# Opto_outputs.net
KiCad netlist of a schematic drawn in Altium Designer
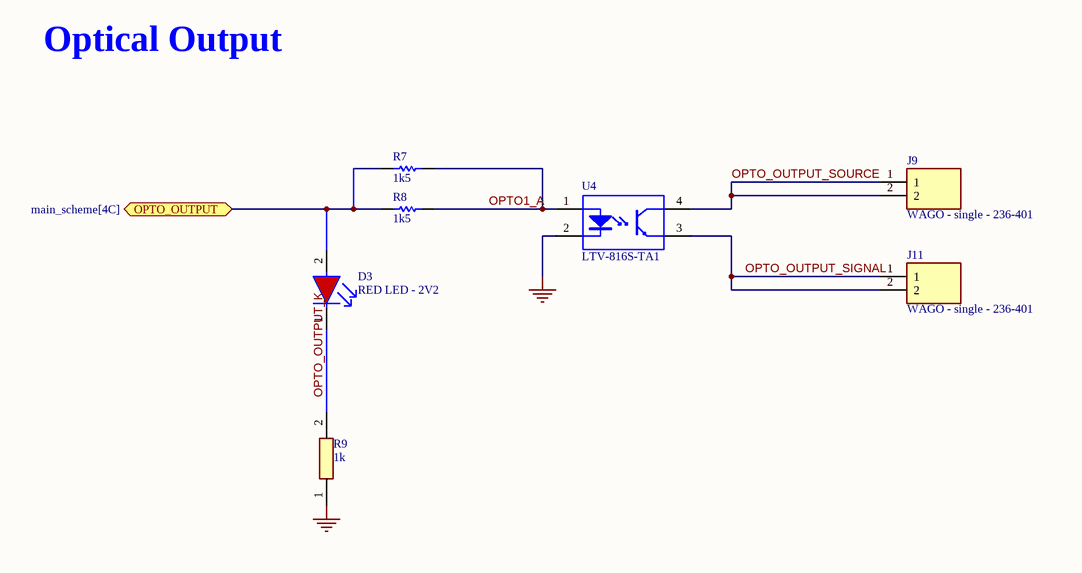
[diagram p0: Opto_outputs.SchDoc]

(export (version "E")
  (design (tool "Eeschema 10.0.6"))
  (components
    (comp (ref "D3")
      (value "RED LED - 2V2")
      (footprint "0603_RED_LED")
      (description "LED RED DIFFUSED 0603 SMD")
      (fields (field (name "PARTNUMBER") "SML-D12U1WT86"))
      (libsource (lib "Schlib1") (part "LED - 0603 - RED - 2V2"))
    )
    (comp (ref "J9")
      (value "WAGO - single - 236-401")
      (footprint "PcbLib1:WAGO-236-601")
      (description "Wago connector - PCB to wire - single - 24A 320V")
      (fields (field (name "PARTNUMBER") "236-401"))
      (libsource (lib "Schlib1") (part "WAGO - single - 236-401"))
    )
    (comp (ref "J11")
      (value "WAGO - single - 236-401")
      (footprint "PcbLib1:WAGO-236-601")
      (description "Wago connector - PCB to wire - single - 24A 320V")
      (fields (field (name "PARTNUMBER") "236-401"))
      (libsource (lib "Schlib1") (part "WAGO - single - 236-401"))
    )
    (comp (ref "R7")
      (value "1k5")
      (footprint "RESC1005X40X25NL05T05")
      (description "Resistor - 0402 - 1k5 - 1% - 100mW")
      (fields (field (name "PARTNUMBER") "ERJ-2RKF1501X"))
      (libsource (lib "Schlib1") (part "Resistor - 0402 - 1k5"))
    )
    (comp (ref "R8")
      (value "1k5")
      (footprint "RESC1005X40X25NL05T05")
      (description "Resistor - 0402 - 1k5 - 1% - 100mW")
      (fields (field (name "PARTNUMBER") "ERJ-2RKF1501X"))
      (libsource (lib "Schlib1") (part "Resistor - 0402 - 1k5"))
    )
    (comp (ref "R9")
      (value "1k")
      (footprint "PcbLib1:0603- SMD resistor")
      (description "Resistor 0603 1KR 100mW 1%")
      (fields (field (name "PARTNUMBER") "RT0603FRE071KL"))
      (libsource (lib "Schlib1") (part "RESISTOR - 0603 - 1k"))
    )
    (comp (ref "U4")
      (value "LTV-816S-TA1")
      (footprint "LTST-LTV-816S_V")
      (description "Photocoupler, 50 mA, -30 to 110 degC, 4-Pin SMD, RoHS, Tape and Reel")
      (libsource (lib "Schlib1") (part "OPTO - 50mA - 80V"))
    )
  )
  (nets
    (net (code "1") (name "/OPTO1_A") (class "Default")
      (node (ref "R7") (pin "2") (pinfunction "2_2") (pintype "passive"))
      (node (ref "R8") (pin "2") (pinfunction "2_2") (pintype "passive"))
      (node (ref "U4") (pin "1") (pinfunction "ANODE_1") (pintype "passive"))
    )
    (net (code "2") (name "/OPTO_OUTPUT") (class "Default")
      (node (ref "D3") (pin "2") (pinfunction "A_2") (pintype "passive"))
      (node (ref "R7") (pin "1") (pinfunction "1_1") (pintype "passive"))
      (node (ref "R8") (pin "1") (pinfunction "1_1") (pintype "passive"))
    )
    (net (code "3") (name "/OPTO_OUTPUT_K") (class "Default")
      (node (ref "D3") (pin "1") (pinfunction "C_1") (pintype "passive"))
      (node (ref "R9") (pin "2") (pinfunction "2_2") (pintype "passive"))
    )
    (net (code "4") (name "/OPTO_OUTPUT_SIGNAL") (class "Default")
      (node (ref "J11") (pin "1") (pinfunction "1_1") (pintype "passive"))
      (node (ref "J11") (pin "2") (pinfunction "2_2") (pintype "passive"))
      (node (ref "U4") (pin "3") (pinfunction "EMITTER_3") (pintype "passive"))
    )
    (net (code "5") (name "/OPTO_OUTPUT_SOURCE") (class "Default")
      (node (ref "J9") (pin "1") (pinfunction "1_1") (pintype "passive"))
      (node (ref "J9") (pin "2") (pinfunction "2_2") (pintype "passive"))
      (node (ref "U4") (pin "4") (pinfunction "COLLECTOR_4") (pintype "passive"))
    )
    (net (code "6") (name "GND") (class "Default")
      (node (ref "R9") (pin "1") (pinfunction "1_1") (pintype "passive"))
      (node (ref "U4") (pin "2") (pinfunction "CATHODE_2") (pintype "passive"))
    )
  )
)
